# Top.net
KiCad netlist of a schematic drawn in Altium Designer
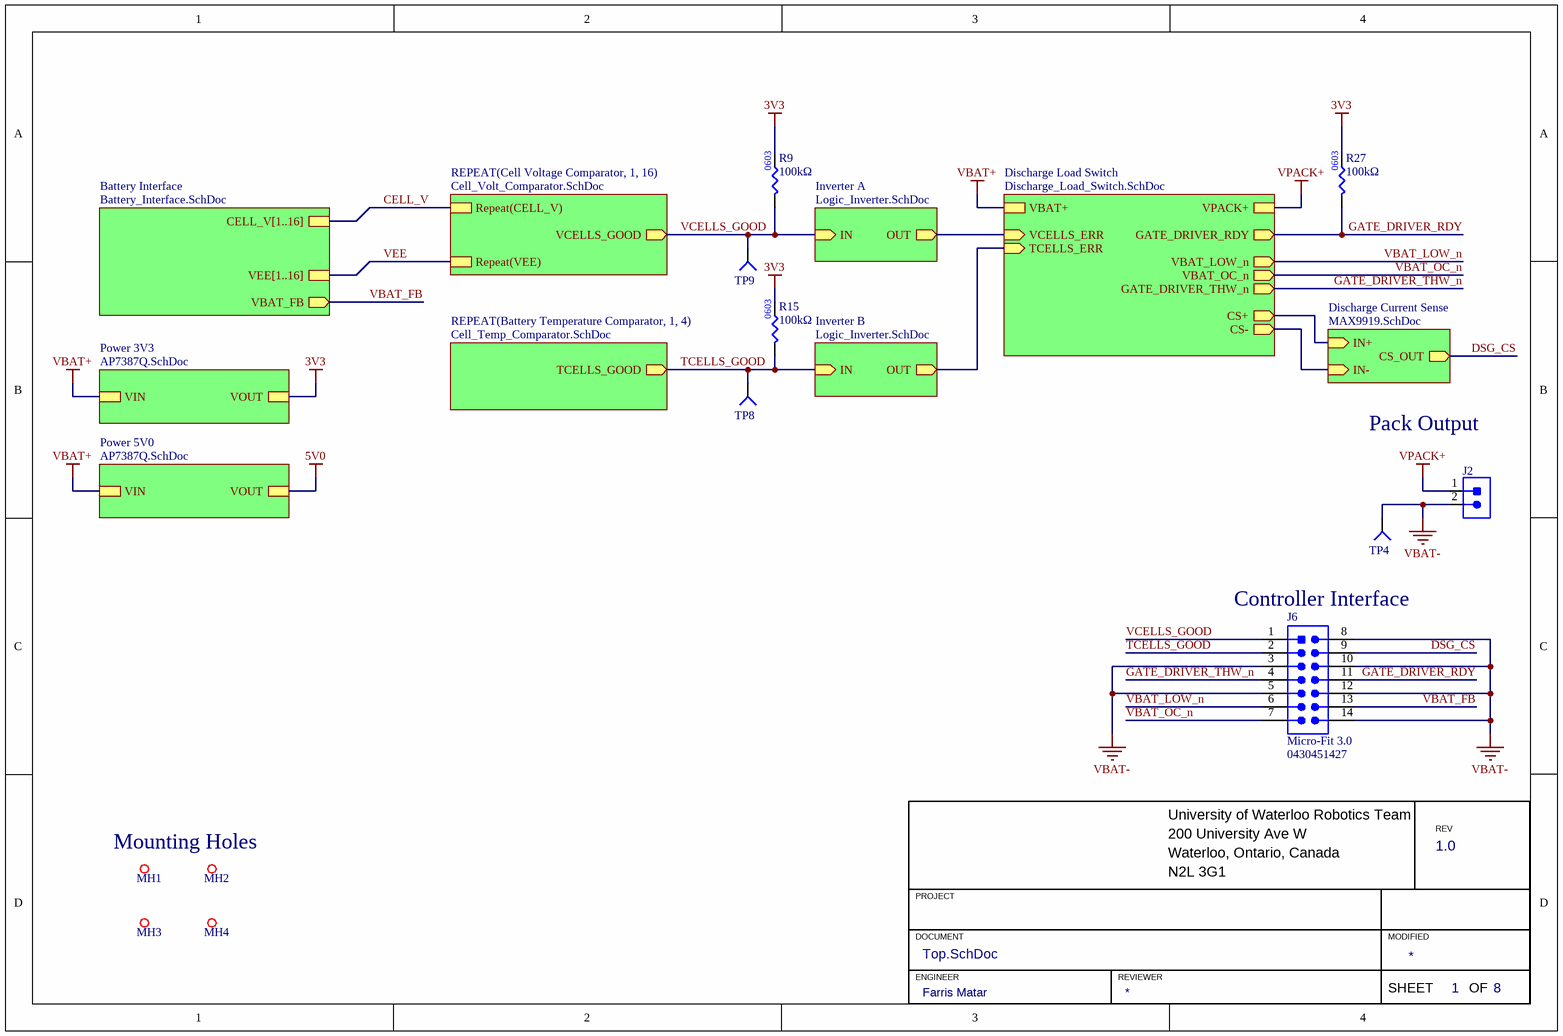
[diagram p0: Top.SchDoc]

(export (version "E")
  (design (tool "Eeschema 10.0.6"))
  (components
    (comp (ref "J2")
      (value "CON_2POS_XT90")
      (footprint "XT90")
      (description "HIGH QUALITY GOLD PLATED XT90 MA")
      (libsource (lib "Personal_Schematic_Library_2022") (part "CON_2POS_XT90"))
    )
    (comp (ref "J6")
      (value "0430451427")
      (footprint "MOLEX-0430451427")
      (description "CONN HEADER VERT 14POS 3MM")
      (fields
        (field (name "FAMILY") "Micro-Fit 3.0")
        (field (name "MANUFACTURER PART NUMBER 1") "0430451427")
      )
      (libsource (lib "Personal_Schematic_Library_2022") (part "CON_MOLEX-HDR_7x2_TH"))
    )
    (comp (ref "MH1")
      (value "MOUNTING_HOLE_M3")
      (footprint "MOUNTING_HOLE_3mm")
      (libsource (lib "UWRT_Schematic_Library_2020") (part "MOUNTING_HOLE_M3"))
    )
    (comp (ref "MH2")
      (value "MOUNTING_HOLE_M3")
      (footprint "MOUNTING_HOLE_3mm")
      (libsource (lib "UWRT_Schematic_Library_2020") (part "MOUNTING_HOLE_M3"))
    )
    (comp (ref "MH3")
      (value "MOUNTING_HOLE_M3")
      (footprint "MOUNTING_HOLE_3mm")
      (libsource (lib "UWRT_Schematic_Library_2020") (part "MOUNTING_HOLE_M3"))
    )
    (comp (ref "MH4")
      (value "MOUNTING_HOLE_M3")
      (footprint "MOUNTING_HOLE_3mm")
      (libsource (lib "UWRT_Schematic_Library_2020") (part "MOUNTING_HOLE_M3"))
    )
    (comp (ref "R9")
      (value "100kΩ")
      (footprint "RES0603")
      (description "RES 100K OHM 1% 1/10W 0603")
      (fields (field (name "Comment") "RES_100kΩ_0603_1%"))
      (libsource (lib "Personal_Schematic_Library_2022") (part "RES_100kΩ_0603_1%"))
    )
    (comp (ref "R15")
      (value "100kΩ")
      (footprint "RES0603")
      (description "RES 100K OHM 1% 1/10W 0603")
      (fields (field (name "Comment") "RES_100kΩ_0603_1%"))
      (libsource (lib "Personal_Schematic_Library_2022") (part "RES_100kΩ_0603_1%"))
    )
    (comp (ref "R27")
      (value "100kΩ")
      (footprint "RES0603")
      (description "RES 100K OHM 1% 1/10W 0603")
      (fields (field (name "Comment") "RES_100kΩ_0603_1%"))
      (libsource (lib "Personal_Schematic_Library_2022") (part "RES_100kΩ_0603_1%"))
    )
    (comp (ref "TP4")
      (value "TESTPOINT_SMD_LOOP")
      (footprint "S1751-46R")
      (description "TESTPOINT SMD LOOP")
      (libsource (lib "UWRT_Schematic_Library_2020") (part "TESTPOINT_SMD_LOOP"))
    )
    (comp (ref "TP8")
      (value "TESTPOINT_1MM_CIRCLE")
      (footprint "TESTPOINT_CIRCLE_1MM")
      (description "TESTPOINT 1MM CIRCLE")
      (libsource (lib "Personal_Schematic_Library_2022") (part "TESTPOINT_1MM_CIRCLE"))
    )
    (comp (ref "TP9")
      (value "TESTPOINT_1MM_CIRCLE")
      (footprint "TESTPOINT_CIRCLE_1MM")
      (description "TESTPOINT 1MM CIRCLE")
      (libsource (lib "Personal_Schematic_Library_2022") (part "TESTPOINT_1MM_CIRCLE"))
    )
  )
  (nets
    (net (code "5") (name "/DSG_CS") (class "Default")
      (node (ref "J6") (pin "9") (pinfunction "9_9") (pintype "passive"))
    )
    (net (code "6") (name "/GATE_DRIVER_RDY") (class "Default")
      (node (ref "J6") (pin "11") (pinfunction "11_11") (pintype "passive"))
      (node (ref "R27") (pin "1") (pinfunction "1_1") (pintype "passive"))
    )
    (net (code "7") (name "/GATE_DRIVER_THW_n") (class "Default")
      (node (ref "J6") (pin "4") (pinfunction "4_4") (pintype "passive"))
    )
    (net (code "10") (name "/TCELLS_GOOD") (class "Default")
      (node (ref "J6") (pin "2") (pinfunction "2_2") (pintype "passive"))
      (node (ref "R15") (pin "1") (pinfunction "1_1") (pintype "passive"))
      (node (ref "TP8") (pin "1") (pinfunction "=value_1") (pintype "passive"))
    )
    (net (code "11") (name "/VBAT_FB") (class "Default")
      (node (ref "J6") (pin "13") (pinfunction "13_13") (pintype "passive"))
    )
    (net (code "12") (name "/VBAT_LOW_n") (class "Default")
      (node (ref "J6") (pin "6") (pinfunction "6_6") (pintype "passive"))
    )
    (net (code "13") (name "/VBAT_OC_n") (class "Default")
      (node (ref "J6") (pin "7") (pinfunction "7_7") (pintype "passive"))
    )
    (net (code "14") (name "/VCELLS_GOOD") (class "Default")
      (node (ref "J6") (pin "1") (pinfunction "1_1") (pintype "passive"))
      (node (ref "R9") (pin "1") (pinfunction "1_1") (pintype "passive"))
      (node (ref "TP9") (pin "1") (pinfunction "=value_1") (pintype "passive"))
    )
    (net (code "17") (name "3V3") (class "Default")
      (node (ref "R15") (pin "2") (pinfunction "2_2") (pintype "passive"))
      (node (ref "R27") (pin "2") (pinfunction "2_2") (pintype "passive"))
      (node (ref "R9") (pin "2") (pinfunction "2_2") (pintype "passive"))
    )
    (net (code "20") (name "VBAT-") (class "Default")
      (node (ref "J2") (pin "2") (pinfunction "2_2") (pintype "passive"))
      (node (ref "J6") (pin "10") (pinfunction "10_10") (pintype "passive"))
      (node (ref "J6") (pin "12") (pinfunction "12_12") (pintype "passive"))
      (node (ref "J6") (pin "14") (pinfunction "14_14") (pintype "passive"))
      (node (ref "J6") (pin "3") (pinfunction "3_3") (pintype "passive"))
      (node (ref "J6") (pin "5") (pinfunction "5_5") (pintype "passive"))
      (node (ref "J6") (pin "8") (pinfunction "8_8") (pintype "passive"))
      (node (ref "TP4") (pin "1") (pinfunction "=value_1") (pintype "passive"))
    )
    (net (code "21") (name "VPACK+") (class "Default")
      (node (ref "J2") (pin "1") (pinfunction "1_1") (pintype "passive"))
    )
  )
)
